# PC104_Connectors.net
KiCad netlist of a schematic drawn in Altium Designer
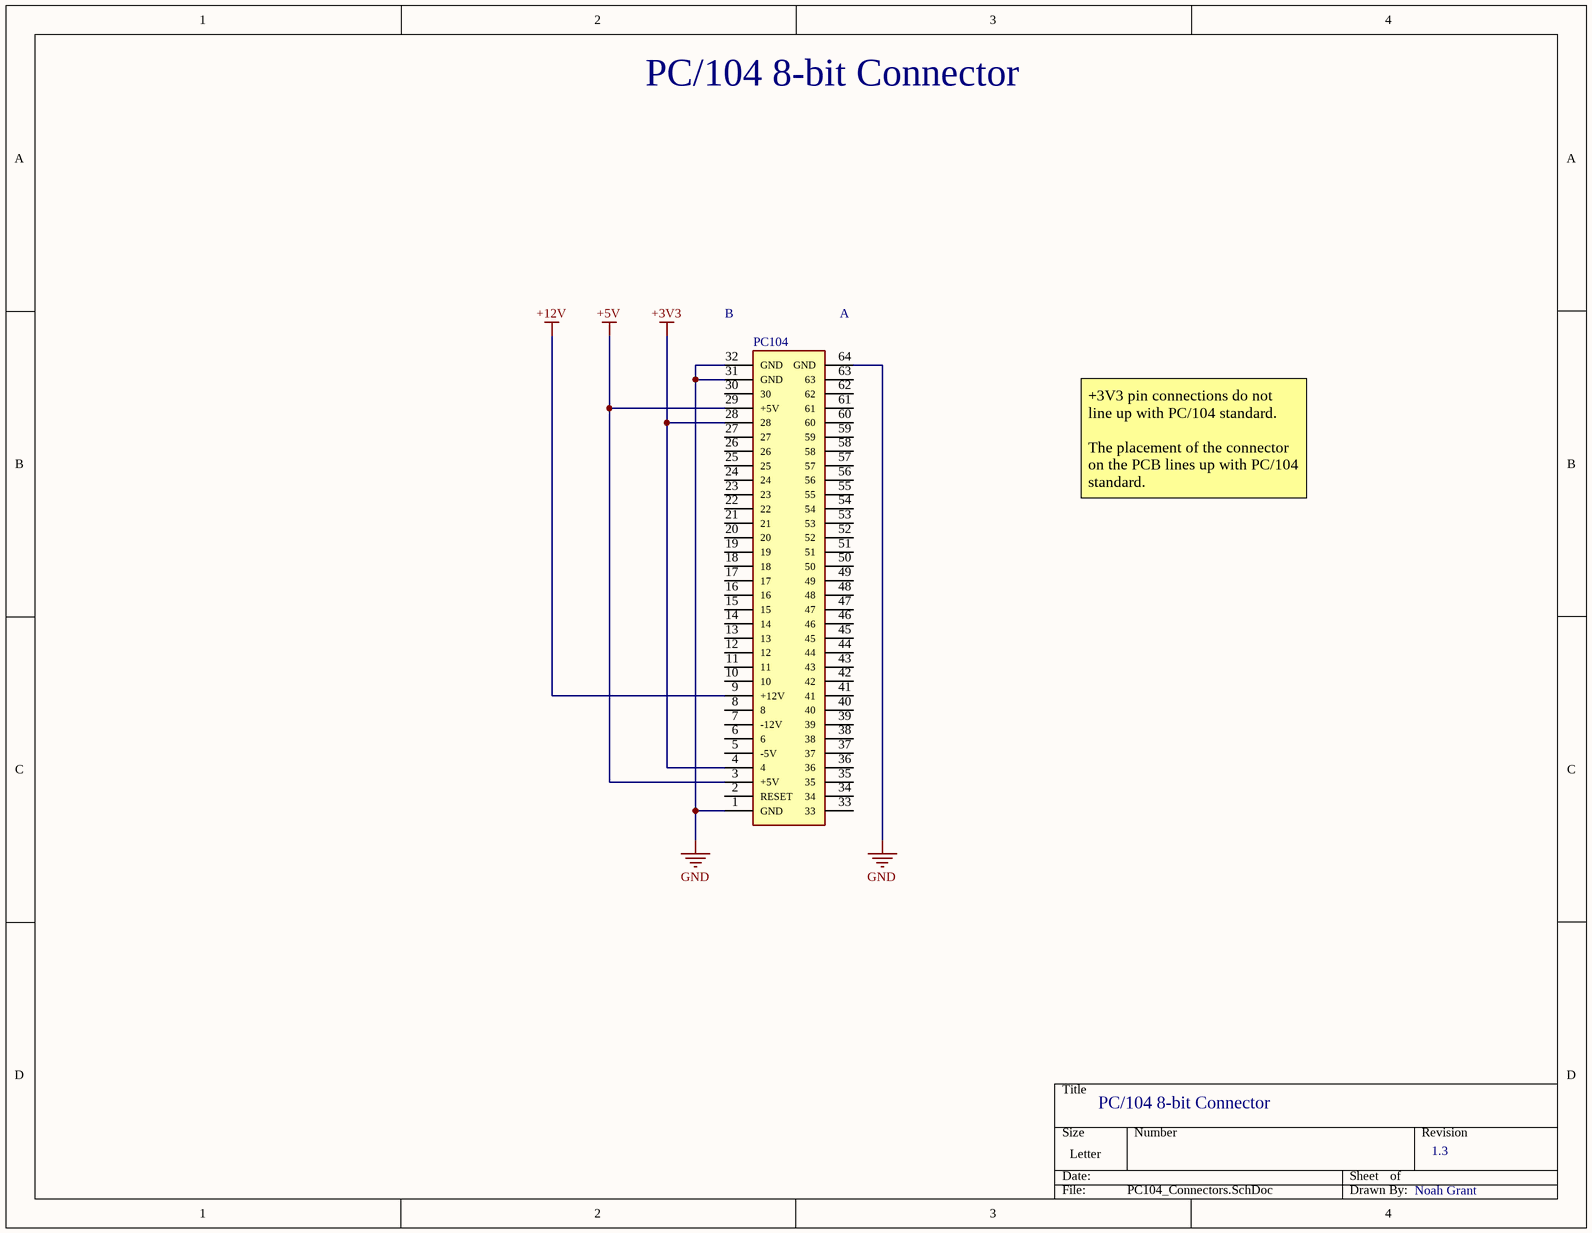
[diagram p0: PC104_Connectors.SchDoc]

(export (version "E")
  (design (tool "Eeschema 10.0.6"))
  (components
    (comp (ref "PC104")
      (value "10153302-32111LF")
      (footprint "SamacSys:RHDR64W74P254_2X32_8238X499X1115P")
      (description "Connector")
      (libsource (lib "*") (part "10153302-32111LF"))
    )
  )
  (nets
    (net (code "1") (name "+3V3") (class "Default")
      (node (ref "PC104") (pin "28") (pinfunction "28_28") (pintype "passive"))
      (node (ref "PC104") (pin "4") (pinfunction "4_4") (pintype "passive"))
    )
    (net (code "2") (name "+5V") (class "Default")
      (node (ref "PC104") (pin "29") (pinfunction "+5V_29") (pintype "passive"))
      (node (ref "PC104") (pin "3") (pinfunction "+5V_3") (pintype "passive"))
    )
    (net (code "3") (name "+12V") (class "Default")
      (node (ref "PC104") (pin "9") (pinfunction "+12V_9") (pintype "passive"))
    )
    (net (code "4") (name "GND") (class "Default")
      (node (ref "PC104") (pin "1") (pinfunction "GND_1") (pintype "passive"))
      (node (ref "PC104") (pin "31") (pinfunction "GND_31") (pintype "passive"))
      (node (ref "PC104") (pin "32") (pinfunction "GND_32") (pintype "passive"))
      (node (ref "PC104") (pin "64") (pinfunction "GND_64") (pintype "passive"))
    )
    (net (code "5") (name "unconnected-(PC104--5V-Pad5)") (class "Default")
      (node (ref "PC104") (pin "5") (pinfunction "-5V_5") (pintype "passive"))
    )
    (net (code "6") (name "unconnected-(PC104--12V-Pad7)") (class "Default")
      (node (ref "PC104") (pin "7") (pinfunction "-12V_7") (pintype "passive"))
    )
    (net (code "7") (name "unconnected-(PC104-Pad6)") (class "Default")
      (node (ref "PC104") (pin "6") (pinfunction "6_6") (pintype "passive"))
    )
    (net (code "8") (name "unconnected-(PC104-Pad8)") (class "Default")
      (node (ref "PC104") (pin "8") (pinfunction "8_8") (pintype "passive"))
    )
    (net (code "9") (name "unconnected-(PC104-Pad10)") (class "Default")
      (node (ref "PC104") (pin "10") (pinfunction "10_10") (pintype "passive"))
    )
    (net (code "10") (name "unconnected-(PC104-Pad11)") (class "Default")
      (node (ref "PC104") (pin "11") (pinfunction "11_11") (pintype "passive"))
    )
    (net (code "11") (name "unconnected-(PC104-Pad12)") (class "Default")
      (node (ref "PC104") (pin "12") (pinfunction "12_12") (pintype "passive"))
    )
    (net (code "12") (name "unconnected-(PC104-Pad13)") (class "Default")
      (node (ref "PC104") (pin "13") (pinfunction "13_13") (pintype "passive"))
    )
    (net (code "13") (name "unconnected-(PC104-Pad14)") (class "Default")
      (node (ref "PC104") (pin "14") (pinfunction "14_14") (pintype "passive"))
    )
    (net (code "14") (name "unconnected-(PC104-Pad15)") (class "Default")
      (node (ref "PC104") (pin "15") (pinfunction "15_15") (pintype "passive"))
    )
    (net (code "15") (name "unconnected-(PC104-Pad16)") (class "Default")
      (node (ref "PC104") (pin "16") (pinfunction "16_16") (pintype "passive"))
    )
    (net (code "16") (name "unconnected-(PC104-Pad17)") (class "Default")
      (node (ref "PC104") (pin "17") (pinfunction "17_17") (pintype "passive"))
    )
    (net (code "17") (name "unconnected-(PC104-Pad18)") (class "Default")
      (node (ref "PC104") (pin "18") (pinfunction "18_18") (pintype "passive"))
    )
    (net (code "18") (name "unconnected-(PC104-Pad19)") (class "Default")
      (node (ref "PC104") (pin "19") (pinfunction "19_19") (pintype "passive"))
    )
    (net (code "19") (name "unconnected-(PC104-Pad20)") (class "Default")
      (node (ref "PC104") (pin "20") (pinfunction "20_20") (pintype "passive"))
    )
    (net (code "20") (name "unconnected-(PC104-Pad21)") (class "Default")
      (node (ref "PC104") (pin "21") (pinfunction "21_21") (pintype "passive"))
    )
    (net (code "21") (name "unconnected-(PC104-Pad22)") (class "Default")
      (node (ref "PC104") (pin "22") (pinfunction "22_22") (pintype "passive"))
    )
    (net (code "22") (name "unconnected-(PC104-Pad23)") (class "Default")
      (node (ref "PC104") (pin "23") (pinfunction "23_23") (pintype "passive"))
    )
    (net (code "23") (name "unconnected-(PC104-Pad24)") (class "Default")
      (node (ref "PC104") (pin "24") (pinfunction "24_24") (pintype "passive"))
    )
    (net (code "24") (name "unconnected-(PC104-Pad25)") (class "Default")
      (node (ref "PC104") (pin "25") (pinfunction "25_25") (pintype "passive"))
    )
    (net (code "25") (name "unconnected-(PC104-Pad26)") (class "Default")
      (node (ref "PC104") (pin "26") (pinfunction "26_26") (pintype "passive"))
    )
    (net (code "26") (name "unconnected-(PC104-Pad27)") (class "Default")
      (node (ref "PC104") (pin "27") (pinfunction "27_27") (pintype "passive"))
    )
    (net (code "27") (name "unconnected-(PC104-Pad30)") (class "Default")
      (node (ref "PC104") (pin "30") (pinfunction "30_30") (pintype "passive"))
    )
    (net (code "28") (name "unconnected-(PC104-Pad33)") (class "Default")
      (node (ref "PC104") (pin "33") (pinfunction "33_33") (pintype "passive"))
    )
    (net (code "29") (name "unconnected-(PC104-Pad34)") (class "Default")
      (node (ref "PC104") (pin "34") (pinfunction "34_34") (pintype "passive"))
    )
    (net (code "30") (name "unconnected-(PC104-Pad35)") (class "Default")
      (node (ref "PC104") (pin "35") (pinfunction "35_35") (pintype "passive"))
    )
    (net (code "31") (name "unconnected-(PC104-Pad36)") (class "Default")
      (node (ref "PC104") (pin "36") (pinfunction "36_36") (pintype "passive"))
    )
    (net (code "32") (name "unconnected-(PC104-Pad37)") (class "Default")
      (node (ref "PC104") (pin "37") (pinfunction "37_37") (pintype "passive"))
    )
    (net (code "33") (name "unconnected-(PC104-Pad38)") (class "Default")
      (node (ref "PC104") (pin "38") (pinfunction "38_38") (pintype "passive"))
    )
    (net (code "34") (name "unconnected-(PC104-Pad39)") (class "Default")
      (node (ref "PC104") (pin "39") (pinfunction "39_39") (pintype "passive"))
    )
    (net (code "35") (name "unconnected-(PC104-Pad40)") (class "Default")
      (node (ref "PC104") (pin "40") (pinfunction "40_40") (pintype "passive"))
    )
    (net (code "36") (name "unconnected-(PC104-Pad41)") (class "Default")
      (node (ref "PC104") (pin "41") (pinfunction "41_41") (pintype "passive"))
    )
    (net (code "37") (name "unconnected-(PC104-Pad42)") (class "Default")
      (node (ref "PC104") (pin "42") (pinfunction "42_42") (pintype "passive"))
    )
    (net (code "38") (name "unconnected-(PC104-Pad43)") (class "Default")
      (node (ref "PC104") (pin "43") (pinfunction "43_43") (pintype "passive"))
    )
    (net (code "39") (name "unconnected-(PC104-Pad44)") (class "Default")
      (node (ref "PC104") (pin "44") (pinfunction "44_44") (pintype "passive"))
    )
    (net (code "40") (name "unconnected-(PC104-Pad45)") (class "Default")
      (node (ref "PC104") (pin "45") (pinfunction "45_45") (pintype "passive"))
    )
    (net (code "41") (name "unconnected-(PC104-Pad46)") (class "Default")
      (node (ref "PC104") (pin "46") (pinfunction "46_46") (pintype "passive"))
    )
    (net (code "42") (name "unconnected-(PC104-Pad47)") (class "Default")
      (node (ref "PC104") (pin "47") (pinfunction "47_47") (pintype "passive"))
    )
    (net (code "43") (name "unconnected-(PC104-Pad48)") (class "Default")
      (node (ref "PC104") (pin "48") (pinfunction "48_48") (pintype "passive"))
    )
    (net (code "44") (name "unconnected-(PC104-Pad49)") (class "Default")
      (node (ref "PC104") (pin "49") (pinfunction "49_49") (pintype "passive"))
    )
    (net (code "45") (name "unconnected-(PC104-Pad50)") (class "Default")
      (node (ref "PC104") (pin "50") (pinfunction "50_50") (pintype "passive"))
    )
    (net (code "46") (name "unconnected-(PC104-Pad51)") (class "Default")
      (node (ref "PC104") (pin "51") (pinfunction "51_51") (pintype "passive"))
    )
    (net (code "47") (name "unconnected-(PC104-Pad52)") (class "Default")
      (node (ref "PC104") (pin "52") (pinfunction "52_52") (pintype "passive"))
    )
    (net (code "48") (name "unconnected-(PC104-Pad53)") (class "Default")
      (node (ref "PC104") (pin "53") (pinfunction "53_53") (pintype "passive"))
    )
    (net (code "49") (name "unconnected-(PC104-Pad54)") (class "Default")
      (node (ref "PC104") (pin "54") (pinfunction "54_54") (pintype "passive"))
    )
    (net (code "50") (name "unconnected-(PC104-Pad55)") (class "Default")
      (node (ref "PC104") (pin "55") (pinfunction "55_55") (pintype "passive"))
    )
    (net (code "51") (name "unconnected-(PC104-Pad56)") (class "Default")
      (node (ref "PC104") (pin "56") (pinfunction "56_56") (pintype "passive"))
    )
    (net (code "52") (name "unconnected-(PC104-Pad57)") (class "Default")
      (node (ref "PC104") (pin "57") (pinfunction "57_57") (pintype "passive"))
    )
    (net (code "53") (name "unconnected-(PC104-Pad58)") (class "Default")
      (node (ref "PC104") (pin "58") (pinfunction "58_58") (pintype "passive"))
    )
    (net (code "54") (name "unconnected-(PC104-Pad59)") (class "Default")
      (node (ref "PC104") (pin "59") (pinfunction "59_59") (pintype "passive"))
    )
    (net (code "55") (name "unconnected-(PC104-Pad60)") (class "Default")
      (node (ref "PC104") (pin "60") (pinfunction "60_60") (pintype "passive"))
    )
    (net (code "56") (name "unconnected-(PC104-Pad61)") (class "Default")
      (node (ref "PC104") (pin "61") (pinfunction "61_61") (pintype "passive"))
    )
    (net (code "57") (name "unconnected-(PC104-Pad62)") (class "Default")
      (node (ref "PC104") (pin "62") (pinfunction "62_62") (pintype "passive"))
    )
    (net (code "58") (name "unconnected-(PC104-Pad63)") (class "Default")
      (node (ref "PC104") (pin "63") (pinfunction "63_63") (pintype "passive"))
    )
    (net (code "59") (name "unconnected-(PC104-RESET-Pad2)") (class "Default")
      (node (ref "PC104") (pin "2") (pinfunction "RESET_2") (pintype "passive"))
    )
  )
)
